# 24V-12V.net
KiCad netlist of a schematic drawn in Altium Designer
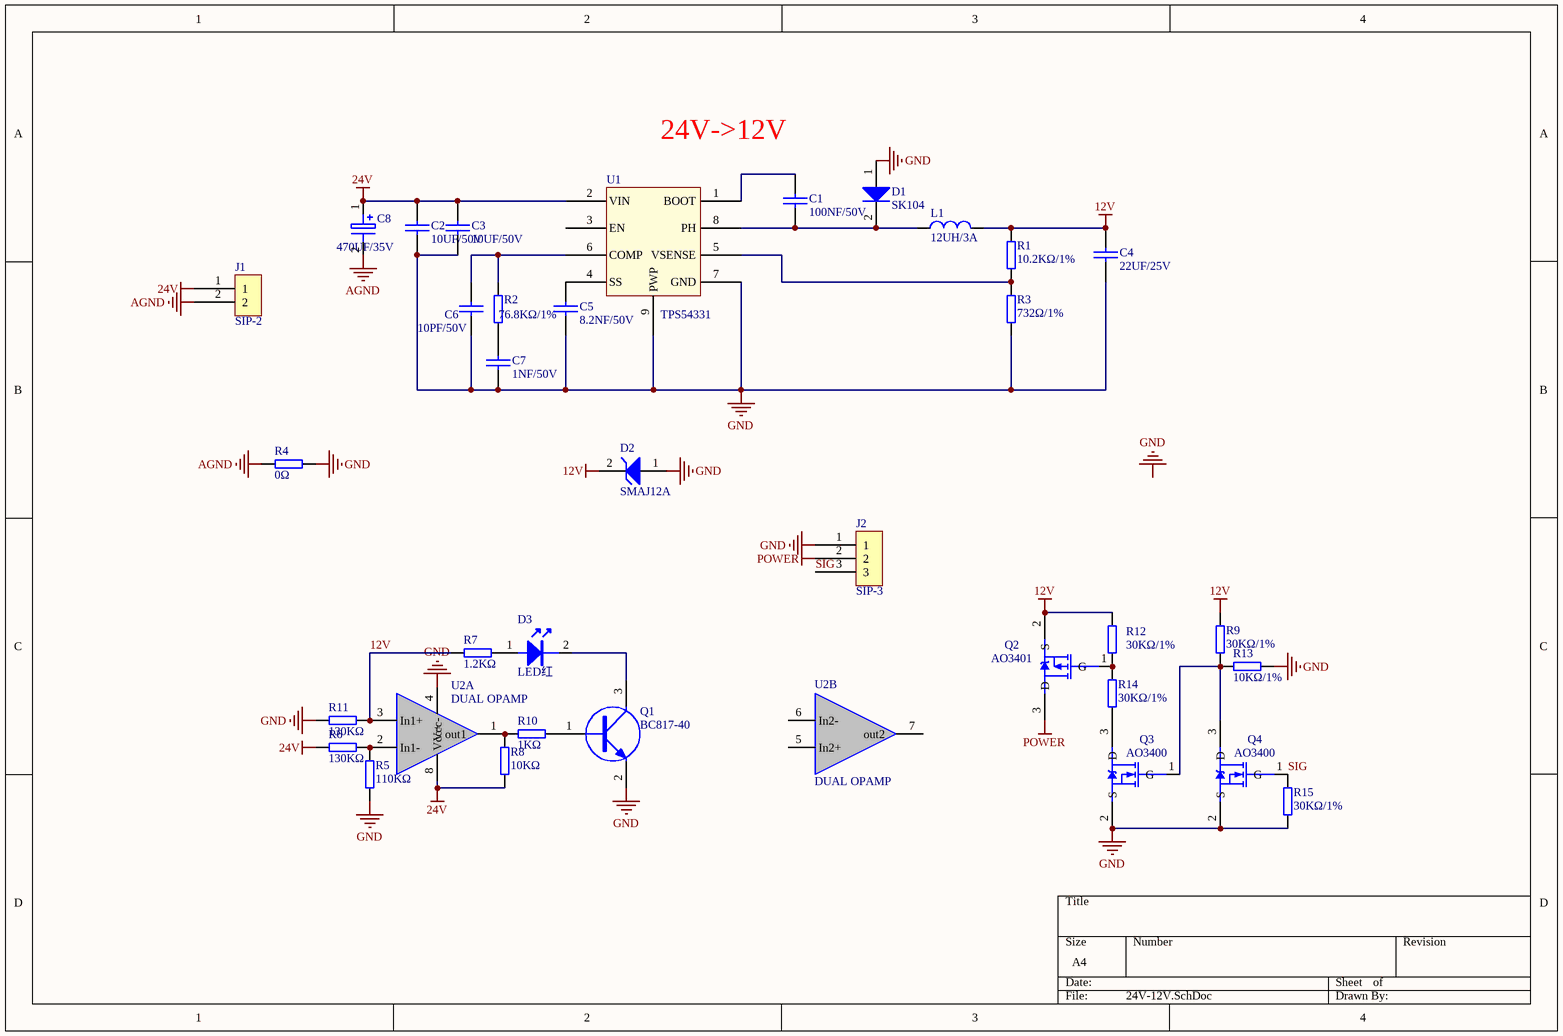
[diagram p0: 24V-12V.SchDoc]

(export (version "E")
  (design (tool "Eeschema 10.0.6"))
  (components
    (comp (ref "C1")
      (value "100NF/50V")
      (footprint "0603_C")
      (description "无极性电容")
      (libsource (lib "Integrated_Library") (part "CAP"))
    )
    (comp (ref "C2")
      (value "10UF/50V")
      (footprint "1206_C")
      (description "无极性电容")
      (libsource (lib "Integrated_Library") (part "CAP"))
    )
    (comp (ref "C3")
      (value "10UF/50V")
      (footprint "1206_C")
      (description "无极性电容")
      (libsource (lib "Integrated_Library") (part "CAP"))
    )
    (comp (ref "C4")
      (value "22UF/25V")
      (footprint "1206_C")
      (description "无极性电容")
      (libsource (lib "Integrated_Library") (part "CAP"))
    )
    (comp (ref "C5")
      (value "8.2NF/50V")
      (footprint "0603_C")
      (description "无极性电容")
      (libsource (lib "Integrated_Library") (part "CAP"))
    )
    (comp (ref "C6")
      (value "10PF/50V")
      (footprint "0603_C")
      (description "无极性电容")
      (libsource (lib "Integrated_Library") (part "CAP"))
    )
    (comp (ref "C7")
      (value "1NF/50V")
      (footprint "0603_C")
      (description "无极性电容")
      (libsource (lib "Integrated_Library") (part "CAP"))
    )
    (comp (ref "C8")
      (value "470UF/35V")
      (footprint "EC-DIP_BD10.0-P5.00-D1.0-FD")
      (description "电解电容")
      (libsource (lib "Integrated_Library") (part "CAP POLAR"))
    )
    (comp (ref "D1")
      (value "SK104")
      (footprint "SMC/DO214AB")
      (description "肖特基二极管/10A")
      (libsource (lib "Integrated_Library") (part "Diodes"))
    )
    (comp (ref "D2")
      (value "SMAJ12A")
      (footprint "SMA/DO214AC")
      (description "5V 单向TVS")
      (fields (field (name "PUBLISHER") "Altium Limited"))
      (libsource (lib "Integrated_Library") (part "Zener diode"))
    )
    (comp (ref "D3")
      (value "LED红")
      (footprint "0603_D")
      (description "发光二极管")
      (libsource (lib "Integrated_Library") (part "LED"))
    )
    (comp (ref "J1")
      (value "SIP-2")
      (footprint "HB611-6.35-2P")
      (description "单排2P插座")
      (libsource (lib "Integrated_Library") (part "SIP-2"))
    )
    (comp (ref "J2")
      (value "SIP-3")
      (footprint "KF2EDGV-3.81-3P")
      (description "单排3P插座")
      (libsource (lib "Integrated_Library") (part "SIP-3"))
    )
    (comp (ref "L1")
      (value "12UH/3A")
      (footprint "IND-SMD_0630")
      (description "电感")
      (libsource (lib "Integrated_Library") (part "INDUCTOR"))
    )
    (comp (ref "Q1")
      (value "BC817-40")
      (footprint "SOT-23-3")
      (description "NPN三极管")
      (libsource (lib "Integrated_Library") (part "BC817-40"))
    )
    (comp (ref "Q2")
      (value "AO3401")
      (footprint "SOT-23-3")
      (description "P-Channel MOSFET")
      (fields (field (name "PUBLISHER") "Altium Limited"))
      (libsource (lib "Integrated_Library") (part "MOSFET_P"))
    )
    (comp (ref "Q3")
      (value "AO3400")
      (footprint "SOT-23-3")
      (description "N-Channel MOSFET")
      (fields (field (name "PUBLISHER") "Altium Limited"))
      (libsource (lib "Integrated_Library") (part "MOSFET-N"))
    )
    (comp (ref "Q4")
      (value "AO3400")
      (footprint "SOT-23-3")
      (description "N-Channel MOSFET")
      (fields (field (name "PUBLISHER") "Altium Limited"))
      (libsource (lib "Integrated_Library") (part "MOSFET-N"))
    )
    (comp (ref "R1")
      (value "10.2KΩ/1%")
      (footprint "0603_R")
      (description "电阻")
      (libsource (lib "Integrated_Library") (part "RES2"))
    )
    (comp (ref "R2")
      (value "76.8KΩ/1%")
      (footprint "0603_R")
      (description "电阻")
      (libsource (lib "Integrated_Library") (part "RES2"))
    )
    (comp (ref "R3")
      (value "732Ω/1%")
      (footprint "0603_R")
      (description "电阻")
      (libsource (lib "Integrated_Library") (part "RES2"))
    )
    (comp (ref "R4")
      (value "0Ω")
      (footprint "1206_R")
      (description "电阻")
      (libsource (lib "Integrated_Library") (part "RES2"))
    )
    (comp (ref "R5")
      (value "110KΩ")
      (footprint "0603_R")
      (description "电阻")
      (libsource (lib "Integrated_Library") (part "RES2"))
    )
    (comp (ref "R6")
      (value "130KΩ")
      (footprint "0603_R")
      (description "电阻")
      (libsource (lib "Integrated_Library") (part "RES2"))
    )
    (comp (ref "R7")
      (value "1.2KΩ")
      (footprint "0805_R")
      (description "电阻")
      (libsource (lib "Integrated_Library") (part "RES2"))
    )
    (comp (ref "R8")
      (value "10KΩ")
      (footprint "0603_R")
      (description "电阻")
      (libsource (lib "Integrated_Library") (part "RES2"))
    )
    (comp (ref "R9")
      (value "30KΩ/1%")
      (footprint "0603_R")
      (description "电阻")
      (libsource (lib "Integrated_Library") (part "RES2"))
    )
    (comp (ref "R10")
      (value "1KΩ")
      (footprint "0603_R")
      (description "电阻")
      (libsource (lib "Integrated_Library") (part "RES2"))
    )
    (comp (ref "R11")
      (value "130KΩ")
      (footprint "0603_R")
      (description "电阻")
      (libsource (lib "Integrated_Library") (part "RES2"))
    )
    (comp (ref "R12")
      (value "30KΩ/1%")
      (footprint "0603_R")
      (description "电阻")
      (libsource (lib "Integrated_Library") (part "RES2"))
    )
    (comp (ref "R13")
      (value "10KΩ/1%")
      (footprint "0603_R")
      (description "电阻")
      (libsource (lib "Integrated_Library") (part "RES2"))
    )
    (comp (ref "R14")
      (value "30KΩ/1%")
      (footprint "0603_R")
      (description "电阻")
      (libsource (lib "Integrated_Library") (part "RES2"))
    )
    (comp (ref "R15")
      (value "30KΩ/1%")
      (footprint "0603_R")
      (description "电阻")
      (libsource (lib "Integrated_Library") (part "RES2"))
    )
    (comp (ref "U1")
      (value "TPS54331")
      (footprint "SO-8-POWERPAD（1.27/3.8*5）")
      (description "DC-DC/5A")
      (libsource (lib "MyLib Schlib") (part "TPS54531"))
    )
    (comp (ref "U2")
      (value "DUAL OPAMP")
      (footprint "SO-8（1.27/3.8*5）")
      (description "双运放")
      (libsource (lib "Integrated_Library") (part "DUAL OPAMP"))
    )
  )
  (nets
    (net (code "1") (name "/SIG") (class "Default")
      (node (ref "J2") (pin "3") (pinfunction "3_3") (pintype "passive"))
      (node (ref "Q4") (pin "1") (pinfunction "G_1") (pintype "passive"))
      (node (ref "R15") (pin "2") (pinfunction "2_2") (pintype "passive"))
    )
    (net (code "2") (name "12V") (class "Default")
      (node (ref "C4") (pin "1") (pinfunction "1_1") (pintype "passive"))
      (node (ref "D2") (pin "2") (pinfunction "K_2") (pintype "passive"))
      (node (ref "L1") (pin "2") (pinfunction "2_2") (pintype "passive"))
      (node (ref "Q2") (pin "2") (pinfunction "S_2") (pintype "passive"))
      (node (ref "R1") (pin "2") (pinfunction "2_2") (pintype "passive"))
      (node (ref "R11") (pin "2") (pinfunction "2_2") (pintype "passive"))
      (node (ref "R12") (pin "1") (pinfunction "1_1") (pintype "passive"))
      (node (ref "R7") (pin "2") (pinfunction "2_2") (pintype "passive"))
      (node (ref "R9") (pin "1") (pinfunction "1_1") (pintype "passive"))
      (node (ref "U2") (pin "3") (pinfunction "In1+_3") (pintype "passive"))
    )
    (net (code "3") (name "24V") (class "Default")
      (node (ref "C2") (pin "1") (pinfunction "1_1") (pintype "passive"))
      (node (ref "C3") (pin "1") (pinfunction "1_1") (pintype "passive"))
      (node (ref "C8") (pin "1") (pinfunction "1_1") (pintype "passive"))
      (node (ref "J1") (pin "1") (pinfunction "1_1") (pintype "passive"))
      (node (ref "R6") (pin "2") (pinfunction "2_2") (pintype "passive"))
      (node (ref "R8") (pin "1") (pinfunction "1_1") (pintype "passive"))
      (node (ref "U1") (pin "2") (pinfunction "VIN_2") (pintype "passive"))
      (node (ref "U2") (pin "8") (pinfunction "Vcc+_8") (pintype "passive"))
    )
    (net (code "4") (name "AGND") (class "Default")
      (node (ref "C8") (pin "2") (pinfunction "2_2") (pintype "passive"))
      (node (ref "J1") (pin "2") (pinfunction "2_2") (pintype "passive"))
      (node (ref "R4") (pin "1") (pinfunction "1_1") (pintype "passive"))
    )
    (net (code "5") (name "GND") (class "Default")
      (node (ref "C2") (pin "2") (pinfunction "2_2") (pintype "passive"))
      (node (ref "C3") (pin "2") (pinfunction "2_2") (pintype "passive"))
      (node (ref "C4") (pin "2") (pinfunction "2_2") (pintype "passive"))
      (node (ref "C5") (pin "2") (pinfunction "2_2") (pintype "passive"))
      (node (ref "C6") (pin "2") (pinfunction "2_2") (pintype "passive"))
      (node (ref "C7") (pin "2") (pinfunction "2_2") (pintype "passive"))
      (node (ref "D1") (pin "1") (pinfunction "A_1") (pintype "passive"))
      (node (ref "D2") (pin "1") (pinfunction "1_1") (pintype "passive"))
      (node (ref "J2") (pin "1") (pinfunction "1_1") (pintype "passive"))
      (node (ref "Q1") (pin "2") (pinfunction "2_2") (pintype "passive"))
      (node (ref "Q3") (pin "2") (pinfunction "S_2") (pintype "passive"))
      (node (ref "Q4") (pin "2") (pinfunction "S_2") (pintype "passive"))
      (node (ref "R11") (pin "1") (pinfunction "1_1") (pintype "passive"))
      (node (ref "R13") (pin "2") (pinfunction "2_2") (pintype "passive"))
      (node (ref "R15") (pin "1") (pinfunction "1_1") (pintype "passive"))
      (node (ref "R3") (pin "1") (pinfunction "1_1") (pintype "passive"))
      (node (ref "R4") (pin "2") (pinfunction "2_2") (pintype "passive"))
      (node (ref "R5") (pin "1") (pinfunction "1_1") (pintype "passive"))
      (node (ref "U1") (pin "7") (pinfunction "GND_7") (pintype "passive"))
      (node (ref "U1") (pin "9") (pinfunction "PWP_9") (pintype "passive"))
      (node (ref "U2") (pin "4") (pinfunction "Vcc-_4") (pintype "passive"))
    )
    (net (code "6") (name "Net-(C7-Pad1)") (class "Default")
      (node (ref "C7") (pin "1") (pinfunction "1_1") (pintype "passive"))
      (node (ref "R2") (pin "1") (pinfunction "1_1") (pintype "passive"))
    )
    (net (code "7") (name "Net-(D1-K)") (class "Default")
      (node (ref "C1") (pin "2") (pinfunction "2_2") (pintype "passive"))
      (node (ref "D1") (pin "2") (pinfunction "K_2") (pintype "passive"))
      (node (ref "L1") (pin "1") (pinfunction "1_1") (pintype "passive"))
      (node (ref "U1") (pin "8") (pinfunction "PH_8") (pintype "passive"))
    )
    (net (code "8") (name "Net-(D3-Pad1)") (class "Default")
      (node (ref "D3") (pin "1") (pinfunction "1_1") (pintype "passive"))
      (node (ref "R7") (pin "1") (pinfunction "1_1") (pintype "passive"))
    )
    (net (code "9") (name "Net-(D3-Pad2)") (class "Default")
      (node (ref "D3") (pin "2") (pinfunction "2_2") (pintype "passive"))
      (node (ref "Q1") (pin "3") (pinfunction "3_3") (pintype "passive"))
    )
    (net (code "10") (name "Net-(Q1-Pad1)") (class "Default")
      (node (ref "Q1") (pin "1") (pinfunction "1_1") (pintype "passive"))
      (node (ref "R10") (pin "2") (pinfunction "2_2") (pintype "passive"))
    )
    (net (code "11") (name "Net-(Q2-G)") (class "Default")
      (node (ref "Q2") (pin "1") (pinfunction "G_1") (pintype "passive"))
      (node (ref "R12") (pin "2") (pinfunction "2_2") (pintype "passive"))
      (node (ref "R14") (pin "1") (pinfunction "1_1") (pintype "passive"))
    )
    (net (code "12") (name "Net-(Q3-D)") (class "Default")
      (node (ref "Q3") (pin "3") (pinfunction "D_3") (pintype "passive"))
      (node (ref "R14") (pin "2") (pinfunction "2_2") (pintype "passive"))
    )
    (net (code "13") (name "Net-(Q3-G)") (class "Default")
      (node (ref "Q3") (pin "1") (pinfunction "G_1") (pintype "passive"))
      (node (ref "Q4") (pin "3") (pinfunction "D_3") (pintype "passive"))
      (node (ref "R13") (pin "1") (pinfunction "1_1") (pintype "passive"))
      (node (ref "R9") (pin "2") (pinfunction "2_2") (pintype "passive"))
    )
    (net (code "14") (name "Net-(U1-BOOT)") (class "Default")
      (node (ref "C1") (pin "1") (pinfunction "1_1") (pintype "passive"))
      (node (ref "U1") (pin "1") (pinfunction "BOOT_1") (pintype "passive"))
    )
    (net (code "15") (name "Net-(U1-COMP)") (class "Default")
      (node (ref "C6") (pin "1") (pinfunction "1_1") (pintype "passive"))
      (node (ref "R2") (pin "2") (pinfunction "2_2") (pintype "passive"))
      (node (ref "U1") (pin "6") (pinfunction "COMP_6") (pintype "passive"))
    )
    (net (code "16") (name "Net-(U1-SS)") (class "Default")
      (node (ref "C5") (pin "1") (pinfunction "1_1") (pintype "passive"))
      (node (ref "U1") (pin "4") (pinfunction "SS_4") (pintype "passive"))
    )
    (net (code "17") (name "Net-(U1-VSENSE)") (class "Default")
      (node (ref "R1") (pin "1") (pinfunction "1_1") (pintype "passive"))
      (node (ref "R3") (pin "2") (pinfunction "2_2") (pintype "passive"))
      (node (ref "U1") (pin "5") (pinfunction "VSENSE_5") (pintype "passive"))
    )
    (net (code "18") (name "Net-(U2A-In1-)") (class "Default")
      (node (ref "R5") (pin "2") (pinfunction "2_2") (pintype "passive"))
      (node (ref "R6") (pin "1") (pinfunction "1_1") (pintype "passive"))
      (node (ref "U2") (pin "2") (pinfunction "In1-_2") (pintype "passive"))
    )
    (net (code "19") (name "Net-(U2A-out1)") (class "Default")
      (node (ref "R10") (pin "1") (pinfunction "1_1") (pintype "passive"))
      (node (ref "R8") (pin "2") (pinfunction "2_2") (pintype "passive"))
      (node (ref "U2") (pin "1") (pinfunction "out1_1") (pintype "passive"))
    )
    (net (code "20") (name "POWER") (class "Default")
      (node (ref "J2") (pin "2") (pinfunction "2_2") (pintype "passive"))
      (node (ref "Q2") (pin "3") (pinfunction "D_3") (pintype "passive"))
    )
    (net (code "21") (name "unconnected-(U1-EN-Pad3)") (class "Default")
      (node (ref "U1") (pin "3") (pinfunction "EN_3") (pintype "passive"))
    )
    (net (code "22") (name "unconnected-(U2B-In2+-Pad5)") (class "Default")
      (node (ref "U2") (pin "5") (pinfunction "In2+_5") (pintype "passive"))
    )
    (net (code "23") (name "unconnected-(U2B-In2--Pad6)") (class "Default")
      (node (ref "U2") (pin "6") (pinfunction "In2-_6") (pintype "passive"))
    )
    (net (code "24") (name "unconnected-(U2B-out2-Pad7)") (class "Default")
      (node (ref "U2") (pin "7") (pinfunction "out2_7") (pintype "passive"))
    )
  )
)
